# Sheet1.net
KiCad netlist of a schematic drawn in Altium Designer
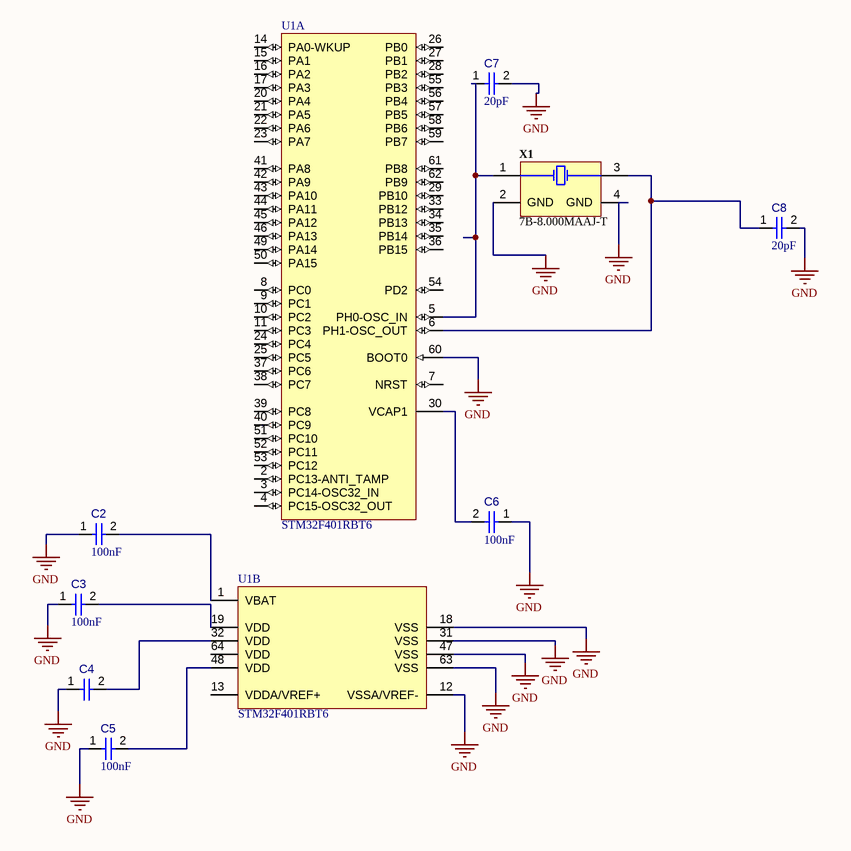
[diagram p0: Sheet1.SchDoc]

(export (version "E")
  (design (tool "Eeschema 10.0.6"))
  (components
    (comp (ref "C2")
      (value "100nF")
      (footprint "CAPC0402(1005)60_L")
      (description "Chip Capacitor, 100nF +/-20%, 50V, 0402, Thickness 0.6 mm")
      (fields (field (name "TOLERANCE") "10%") (field (name "Comment") "Capacitor 100nF +/-20% 50V 0402"))
      (libsource (lib "Menna Waleed") (part "CAP-NP-2"))
    )
    (comp (ref "C3")
      (value "100nF")
      (footprint "CAPC0402(1005)60_L")
      (description "Chip Capacitor, 100nF +/-20%, 50V, 0402, Thickness 0.6 mm")
      (fields (field (name "TOLERANCE") "10%") (field (name "Comment") "Capacitor 100nF +/-20% 50V 0402"))
      (libsource (lib "Menna Waleed") (part "CAP-NP-2"))
    )
    (comp (ref "C4")
      (value "Capacitor 100nF +/-20% 50V 0402")
      (footprint "CAPC0402(1005)60_L")
      (description "Chip Capacitor, 100nF +/-20%, 50V, 0402, Thickness 0.6 mm")
      (fields (field (name "TOLERANCE") "10%"))
      (libsource (lib "Menna Waleed") (part "CAP-NP-2"))
    )
    (comp (ref "C5")
      (value "100nF")
      (footprint "CAPC0402(1005)60_L")
      (description "Chip Capacitor, 100nF +/-20%, 50V, 0402, Thickness 0.6 mm")
      (fields (field (name "TOLERANCE") "10%") (field (name "Comment") "Capacitor 100nF +/-20% 50V 0402"))
      (libsource (lib "Menna Waleed") (part "CAP-NP-2"))
    )
    (comp (ref "C6")
      (value "100nF")
      (footprint "CAPC0402(1005)60_L")
      (description "Chip Capacitor, 100nF +/-20%, 50V, 0402, Thickness 0.6 mm")
      (fields (field (name "TOLERANCE") "10%") (field (name "Comment") "Capacitor 100nF +/-20% 50V 0402"))
      (libsource (lib "") (part "CAP-NP-2_1"))
    )
    (comp (ref "C7")
      (value "20pF")
      (footprint "CAPC0402(1005)60_L")
      (description "Chip Capacitor, 100nF +/-20%, 50V, 0402, Thickness 0.6 mm")
      (fields (field (name "TOLERANCE") "10%") (field (name "Comment") "Capacitor 100nF +/-20% 50V 0402"))
      (libsource (lib "Menna Waleed") (part "CAP-NP-2"))
    )
    (comp (ref "C8")
      (value "20pF")
      (footprint "CAPC0402(1005)60_L")
      (description "Chip Capacitor, 100nF +/-20%, 50V, 0402, Thickness 0.6 mm")
      (fields (field (name "TOLERANCE") "10%") (field (name "Comment") "Capacitor 100nF +/-20% 50V 0402"))
      (libsource (lib "Menna Waleed") (part "CAP-NP-2"))
    )
    (comp (ref "U1")
      (value "STM32F401RBT6")
      (footprint "STM-LQFP64_M")
      (description "ARM Cortex -M4 32b MCU+FPU, 256 KB Flash, 64 KB RAM, -40 to 85 degC, 64-Pin LQFP, RoHS, Tray")
      (fields (field (name "POWER") "313mW") (field (name "MANUFACTURER") "STMicroelectronics"))
      (libsource (lib "") (part "MC-ARM-STM32F401-SQ64_1"))
    )
    (comp (ref "X1")
      (value "7B-8.000MAAJ-T")
      (footprint "TXC-7B-4_V")
      (description "SMD Seam Sealing Crystal, 8 MHz, +/- 30 ppm, 18 pF, -10 to 70 degC, 4-Pin SMD, RoHS, Tape and Reel")
      (fields (field (name "MANUFACTURER") "TXC") (field (name "TOLERANCE") "30ppm"))
      (libsource (lib "Menna Waleed") (part "XTAL-1-3-4"))
    )
  )
  (nets
    (net (code "1") (name "GND") (class "Default")
      (node (ref "C2") (pin "1") (pinfunction "1_1") (pintype "passive"))
      (node (ref "C3") (pin "1") (pinfunction "1_1") (pintype "passive"))
      (node (ref "C4") (pin "1") (pinfunction "1_1") (pintype "passive"))
      (node (ref "C5") (pin "1") (pinfunction "1_1") (pintype "passive"))
      (node (ref "C6") (pin "1") (pinfunction "1_1") (pintype "passive"))
      (node (ref "C7") (pin "2") (pinfunction "2_2") (pintype "passive"))
      (node (ref "C8") (pin "2") (pinfunction "2_2") (pintype "passive"))
      (node (ref "U1") (pin "12") (pinfunction "VSSA/VREF-_12") (pintype "power_in"))
      (node (ref "U1") (pin "18") (pinfunction "VSS_18") (pintype "power_in"))
      (node (ref "U1") (pin "31") (pinfunction "VSS_31") (pintype "power_in"))
      (node (ref "U1") (pin "47") (pinfunction "VSS_47") (pintype "power_in"))
      (node (ref "U1") (pin "60") (pinfunction "BOOT0_60") (pintype "input"))
      (node (ref "U1") (pin "63") (pinfunction "VSS_63") (pintype "power_in"))
      (node (ref "X1") (pin "2") (pinfunction "GND_2") (pintype "power_in"))
      (node (ref "X1") (pin "4") (pinfunction "GND_4") (pintype "power_in"))
    )
    (net (code "2") (name "Net-(C3-Pad2)") (class "Default")
      (node (ref "C3") (pin "2") (pinfunction "2_2") (pintype "passive"))
      (node (ref "U1") (pin "19") (pinfunction "VDD_19") (pintype "power_in"))
    )
    (net (code "3") (name "Net-(C4-Pad2)") (class "Default")
      (node (ref "C4") (pin "2") (pinfunction "2_2") (pintype "passive"))
      (node (ref "U1") (pin "32") (pinfunction "VDD_32") (pintype "power_in"))
    )
    (net (code "4") (name "Net-(C5-Pad2)") (class "Default")
      (node (ref "C5") (pin "2") (pinfunction "2_2") (pintype "passive"))
      (node (ref "U1") (pin "48") (pinfunction "VDD_48") (pintype "power_in"))
    )
    (net (code "5") (name "Net-(U1A-PH0-OSC_IN)") (class "Default")
      (node (ref "C7") (pin "1") (pinfunction "1_1") (pintype "passive"))
      (node (ref "U1") (pin "5") (pinfunction "PH0-OSC_IN_5") (pintype "bidirectional"))
      (node (ref "X1") (pin "1") (pinfunction "X1_1") (pintype "passive"))
    )
    (net (code "6") (name "Net-(U1A-PH1-OSC_OUT)") (class "Default")
      (node (ref "C8") (pin "1") (pinfunction "1_1") (pintype "passive"))
      (node (ref "U1") (pin "6") (pinfunction "PH1-OSC_OUT_6") (pintype "bidirectional"))
      (node (ref "X1") (pin "3") (pinfunction "X2_3") (pintype "passive"))
    )
    (net (code "7") (name "Net-(U1A-VCAP1)") (class "Default")
      (node (ref "C6") (pin "2") (pinfunction "2_2") (pintype "passive"))
      (node (ref "U1") (pin "30") (pinfunction "VCAP1_30") (pintype "power_in"))
    )
    (net (code "8") (name "Net-(U1B-VBAT)") (class "Default")
      (node (ref "C2") (pin "2") (pinfunction "2_2") (pintype "passive"))
      (node (ref "U1") (pin "1") (pinfunction "VBAT_1") (pintype "power_in"))
    )
    (net (code "9") (name "unconnected-(U1A-NRST-Pad7)") (class "Default")
      (node (ref "U1") (pin "7") (pinfunction "NRST_7") (pintype "bidirectional"))
    )
    (net (code "10") (name "unconnected-(U1A-PA0-WKUP-Pad14)") (class "Default")
      (node (ref "U1") (pin "14") (pinfunction "PA0-WKUP_14") (pintype "bidirectional"))
    )
    (net (code "11") (name "unconnected-(U1A-PA1-Pad15)") (class "Default")
      (node (ref "U1") (pin "15") (pinfunction "PA1_15") (pintype "bidirectional"))
    )
    (net (code "12") (name "unconnected-(U1A-PA2-Pad16)") (class "Default")
      (node (ref "U1") (pin "16") (pinfunction "PA2_16") (pintype "bidirectional"))
    )
    (net (code "13") (name "unconnected-(U1A-PA3-Pad17)") (class "Default")
      (node (ref "U1") (pin "17") (pinfunction "PA3_17") (pintype "bidirectional"))
    )
    (net (code "14") (name "unconnected-(U1A-PA4-Pad20)") (class "Default")
      (node (ref "U1") (pin "20") (pinfunction "PA4_20") (pintype "bidirectional"))
    )
    (net (code "15") (name "unconnected-(U1A-PA5-Pad21)") (class "Default")
      (node (ref "U1") (pin "21") (pinfunction "PA5_21") (pintype "bidirectional"))
    )
    (net (code "16") (name "unconnected-(U1A-PA6-Pad22)") (class "Default")
      (node (ref "U1") (pin "22") (pinfunction "PA6_22") (pintype "bidirectional"))
    )
    (net (code "17") (name "unconnected-(U1A-PA7-Pad23)") (class "Default")
      (node (ref "U1") (pin "23") (pinfunction "PA7_23") (pintype "bidirectional"))
    )
    (net (code "18") (name "unconnected-(U1A-PA8-Pad41)") (class "Default")
      (node (ref "U1") (pin "41") (pinfunction "PA8_41") (pintype "bidirectional"))
    )
    (net (code "19") (name "unconnected-(U1A-PA9-Pad42)") (class "Default")
      (node (ref "U1") (pin "42") (pinfunction "PA9_42") (pintype "bidirectional"))
    )
    (net (code "20") (name "unconnected-(U1A-PA10-Pad43)") (class "Default")
      (node (ref "U1") (pin "43") (pinfunction "PA10_43") (pintype "bidirectional"))
    )
    (net (code "21") (name "unconnected-(U1A-PA11-Pad44)") (class "Default")
      (node (ref "U1") (pin "44") (pinfunction "PA11_44") (pintype "bidirectional"))
    )
    (net (code "22") (name "unconnected-(U1A-PA12-Pad45)") (class "Default")
      (node (ref "U1") (pin "45") (pinfunction "PA12_45") (pintype "bidirectional"))
    )
    (net (code "23") (name "unconnected-(U1A-PA13-Pad46)") (class "Default")
      (node (ref "U1") (pin "46") (pinfunction "PA13_46") (pintype "bidirectional"))
    )
    (net (code "24") (name "unconnected-(U1A-PA14-Pad49)") (class "Default")
      (node (ref "U1") (pin "49") (pinfunction "PA14_49") (pintype "bidirectional"))
    )
    (net (code "25") (name "unconnected-(U1A-PA15-Pad50)") (class "Default")
      (node (ref "U1") (pin "50") (pinfunction "PA15_50") (pintype "bidirectional"))
    )
    (net (code "26") (name "unconnected-(U1A-PB0-Pad26)") (class "Default")
      (node (ref "U1") (pin "26") (pinfunction "PB0_26") (pintype "bidirectional"))
    )
    (net (code "27") (name "unconnected-(U1A-PB1-Pad27)") (class "Default")
      (node (ref "U1") (pin "27") (pinfunction "PB1_27") (pintype "bidirectional"))
    )
    (net (code "28") (name "unconnected-(U1A-PB2-Pad28)") (class "Default")
      (node (ref "U1") (pin "28") (pinfunction "PB2_28") (pintype "bidirectional"))
    )
    (net (code "29") (name "unconnected-(U1A-PB3-Pad55)") (class "Default")
      (node (ref "U1") (pin "55") (pinfunction "PB3_55") (pintype "bidirectional"))
    )
    (net (code "30") (name "unconnected-(U1A-PB4-Pad56)") (class "Default")
      (node (ref "U1") (pin "56") (pinfunction "PB4_56") (pintype "bidirectional"))
    )
    (net (code "31") (name "unconnected-(U1A-PB5-Pad57)") (class "Default")
      (node (ref "U1") (pin "57") (pinfunction "PB5_57") (pintype "bidirectional"))
    )
    (net (code "32") (name "unconnected-(U1A-PB6-Pad58)") (class "Default")
      (node (ref "U1") (pin "58") (pinfunction "PB6_58") (pintype "bidirectional"))
    )
    (net (code "33") (name "unconnected-(U1A-PB7-Pad59)") (class "Default")
      (node (ref "U1") (pin "59") (pinfunction "PB7_59") (pintype "bidirectional"))
    )
    (net (code "34") (name "unconnected-(U1A-PB8-Pad61)") (class "Default")
      (node (ref "U1") (pin "61") (pinfunction "PB8_61") (pintype "bidirectional"))
    )
    (net (code "35") (name "unconnected-(U1A-PB9-Pad62)") (class "Default")
      (node (ref "U1") (pin "62") (pinfunction "PB9_62") (pintype "bidirectional"))
    )
    (net (code "36") (name "unconnected-(U1A-PB10-Pad29)") (class "Default")
      (node (ref "U1") (pin "29") (pinfunction "PB10_29") (pintype "bidirectional"))
    )
    (net (code "37") (name "unconnected-(U1A-PB12-Pad33)") (class "Default")
      (node (ref "U1") (pin "33") (pinfunction "PB12_33") (pintype "bidirectional"))
    )
    (net (code "38") (name "unconnected-(U1A-PB13-Pad34)") (class "Default")
      (node (ref "U1") (pin "34") (pinfunction "PB13_34") (pintype "bidirectional"))
    )
    (net (code "39") (name "unconnected-(U1A-PB14-Pad35)") (class "Default")
      (node (ref "U1") (pin "35") (pinfunction "PB14_35") (pintype "bidirectional"))
    )
    (net (code "40") (name "unconnected-(U1A-PB15-Pad36)") (class "Default")
      (node (ref "U1") (pin "36") (pinfunction "PB15_36") (pintype "bidirectional"))
    )
    (net (code "41") (name "unconnected-(U1A-PC0-Pad8)") (class "Default")
      (node (ref "U1") (pin "8") (pinfunction "PC0_8") (pintype "bidirectional"))
    )
    (net (code "42") (name "unconnected-(U1A-PC1-Pad9)") (class "Default")
      (node (ref "U1") (pin "9") (pinfunction "PC1_9") (pintype "bidirectional"))
    )
    (net (code "43") (name "unconnected-(U1A-PC2-Pad10)") (class "Default")
      (node (ref "U1") (pin "10") (pinfunction "PC2_10") (pintype "bidirectional"))
    )
    (net (code "44") (name "unconnected-(U1A-PC3-Pad11)") (class "Default")
      (node (ref "U1") (pin "11") (pinfunction "PC3_11") (pintype "bidirectional"))
    )
    (net (code "45") (name "unconnected-(U1A-PC4-Pad24)") (class "Default")
      (node (ref "U1") (pin "24") (pinfunction "PC4_24") (pintype "bidirectional"))
    )
    (net (code "46") (name "unconnected-(U1A-PC5-Pad25)") (class "Default")
      (node (ref "U1") (pin "25") (pinfunction "PC5_25") (pintype "bidirectional"))
    )
    (net (code "47") (name "unconnected-(U1A-PC6-Pad37)") (class "Default")
      (node (ref "U1") (pin "37") (pinfunction "PC6_37") (pintype "bidirectional"))
    )
    (net (code "48") (name "unconnected-(U1A-PC7-Pad38)") (class "Default")
      (node (ref "U1") (pin "38") (pinfunction "PC7_38") (pintype "bidirectional"))
    )
    (net (code "49") (name "unconnected-(U1A-PC8-Pad39)") (class "Default")
      (node (ref "U1") (pin "39") (pinfunction "PC8_39") (pintype "bidirectional"))
    )
    (net (code "50") (name "unconnected-(U1A-PC9-Pad40)") (class "Default")
      (node (ref "U1") (pin "40") (pinfunction "PC9_40") (pintype "bidirectional"))
    )
    (net (code "51") (name "unconnected-(U1A-PC10-Pad51)") (class "Default")
      (node (ref "U1") (pin "51") (pinfunction "PC10_51") (pintype "bidirectional"))
    )
    (net (code "52") (name "unconnected-(U1A-PC11-Pad52)") (class "Default")
      (node (ref "U1") (pin "52") (pinfunction "PC11_52") (pintype "bidirectional"))
    )
    (net (code "53") (name "unconnected-(U1A-PC12-Pad53)") (class "Default")
      (node (ref "U1") (pin "53") (pinfunction "PC12_53") (pintype "bidirectional"))
    )
    (net (code "54") (name "unconnected-(U1A-PC13-ANTI_TAMP-Pad2)") (class "Default")
      (node (ref "U1") (pin "2") (pinfunction "PC13-ANTI_TAMP_2") (pintype "bidirectional"))
    )
    (net (code "55") (name "unconnected-(U1A-PC14-OSC32_IN-Pad3)") (class "Default")
      (node (ref "U1") (pin "3") (pinfunction "PC14-OSC32_IN_3") (pintype "bidirectional"))
    )
    (net (code "56") (name "unconnected-(U1A-PC15-OSC32_OUT-Pad4)") (class "Default")
      (node (ref "U1") (pin "4") (pinfunction "PC15-OSC32_OUT_4") (pintype "bidirectional"))
    )
    (net (code "57") (name "unconnected-(U1A-PD2-Pad54)") (class "Default")
      (node (ref "U1") (pin "54") (pinfunction "PD2_54") (pintype "bidirectional"))
    )
    (net (code "58") (name "unconnected-(U1B-VDD-Pad64)") (class "Default")
      (node (ref "U1") (pin "64") (pinfunction "VDD_64") (pintype "power_in"))
    )
    (net (code "59") (name "unconnected-(U1B-VDDA{slash}VREF+-Pad13)") (class "Default")
      (node (ref "U1") (pin "13") (pinfunction "VDDA/VREF+_13") (pintype "power_in"))
    )
  )
)
